# B12356-04b.net
KiCad netlist of a schematic drawn in EAGLE
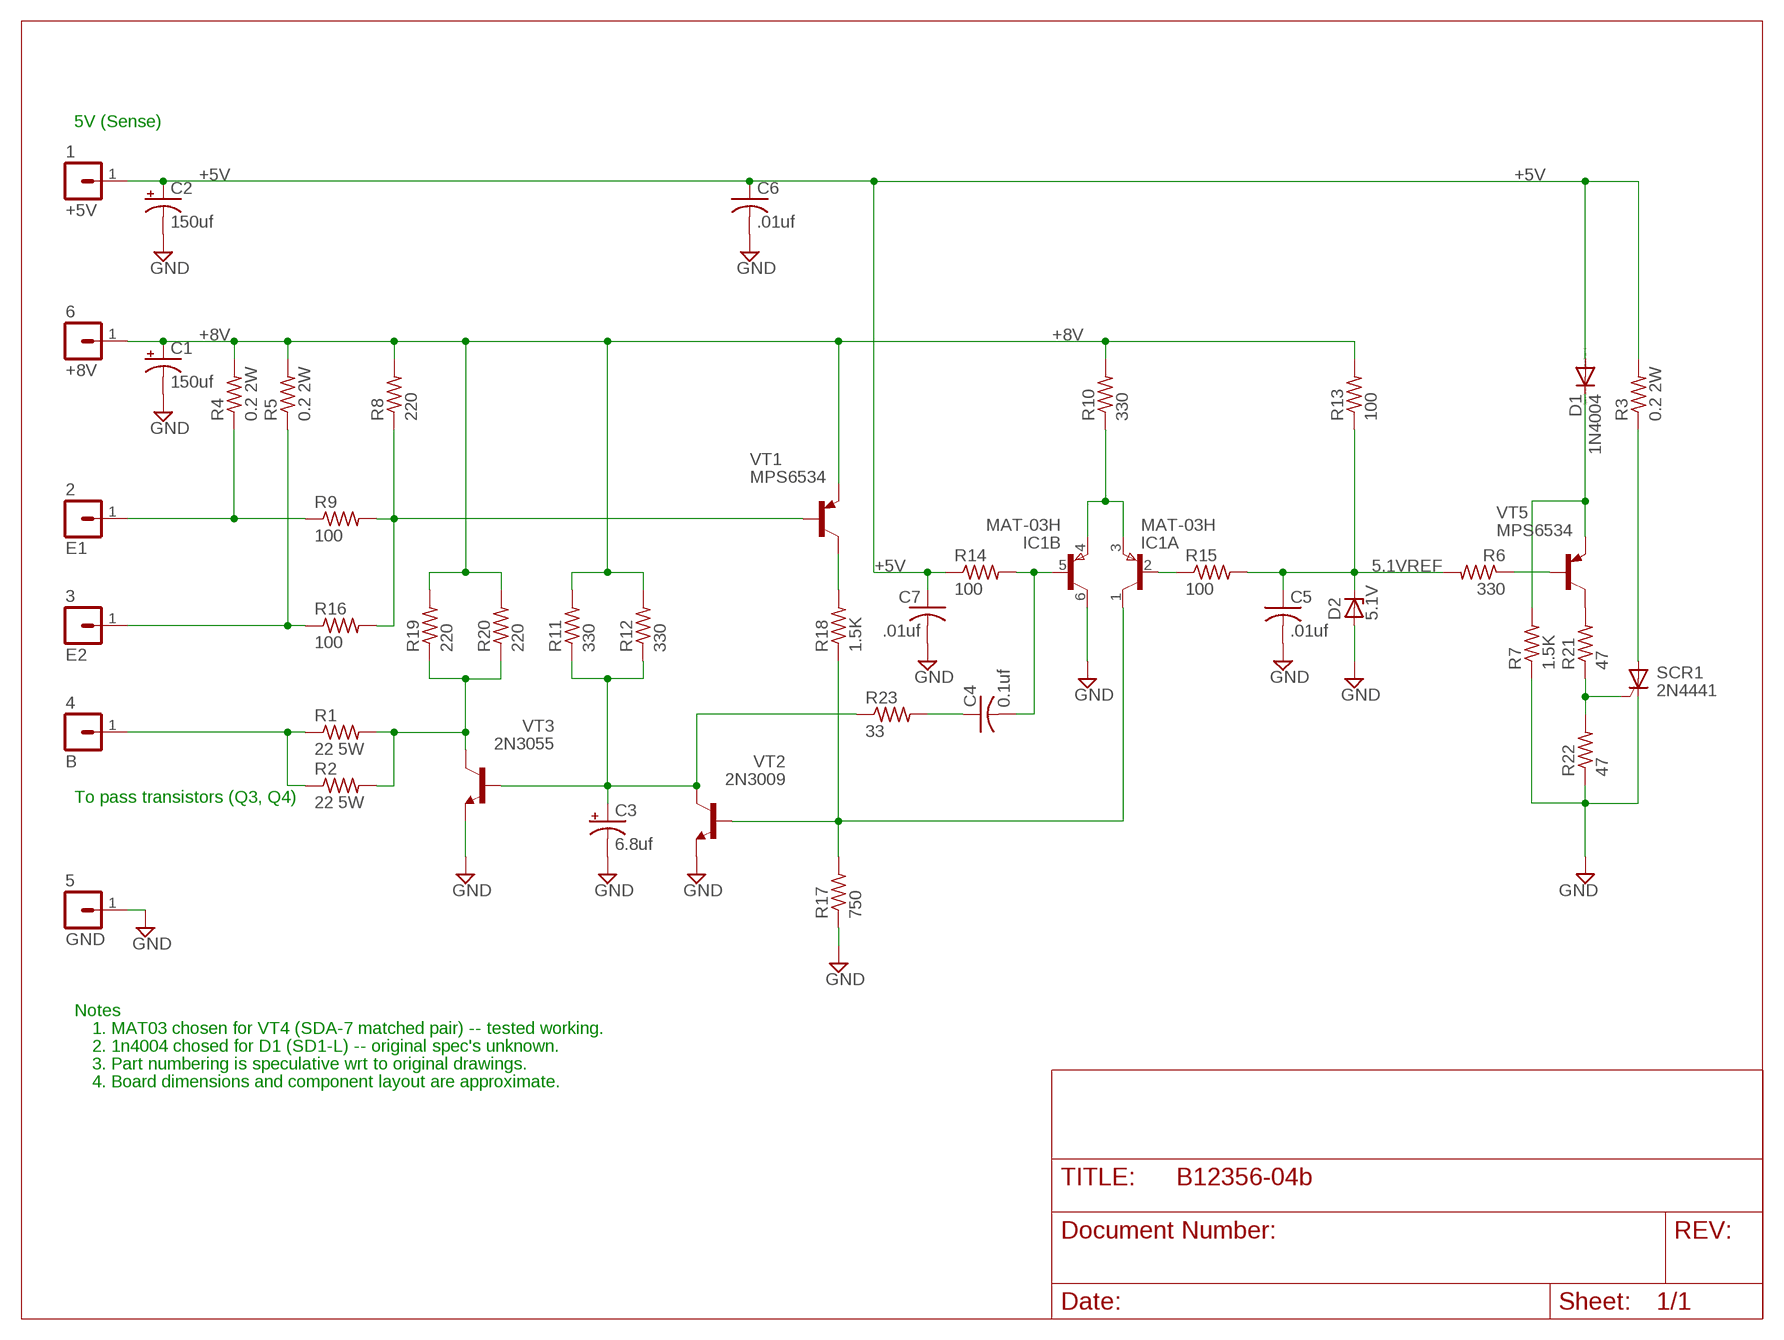
[diagram p0: schematic, sheet 1]

(export (version "E")
  (design (tool "Eeschema 10.0.6"))
  (components
    (comp (ref "+5V")
      (value "1")
      (footprint "eagle-import:SPADELUG")
      (libsource (lib "eagle-import") (part "LUG"))
    )
    (comp (ref "+8V")
      (value "6")
      (footprint "eagle-import:SPADELUG")
      (libsource (lib "eagle-import") (part "LUG"))
    )
    (comp (ref "B")
      (value "4")
      (footprint "eagle-import:SPADELUG")
      (libsource (lib "eagle-import") (part "LUG"))
    )
    (comp (ref "C1")
      (value "150uf")
      (footprint "eagle-import:E30-10")
      (libsource (lib "eagle-import") (part "CPOL-USE30-10AXIAL"))
    )
    (comp (ref "C2")
      (value "150uf")
      (footprint "eagle-import:E25-9")
      (libsource (lib "eagle-import") (part "CPOL-USE25-9AXIAL"))
    )
    (comp (ref "C3")
      (value "6.8uf")
      (footprint "eagle-import:E22-6")
      (libsource (lib "eagle-import") (part "CPOL-USE22-6AXIAL"))
    )
    (comp (ref "C4")
      (value "0.1uf")
      (footprint "eagle-import:C150-054X183")
      (libsource (lib "eagle-import") (part "C-US150-054X183"))
    )
    (comp (ref "C5")
      (value ".01uf")
      (footprint "eagle-import:C050-025X075")
      (libsource (lib "eagle-import") (part "C-US050-025X075"))
    )
    (comp (ref "C6")
      (value ".01uf")
      (footprint "eagle-import:C050-025X075")
      (libsource (lib "eagle-import") (part "C-US050-025X075"))
    )
    (comp (ref "C7")
      (value ".01uf")
      (footprint "eagle-import:C050-025X075")
      (libsource (lib "eagle-import") (part "C-US050-025X075"))
    )
    (comp (ref "D1")
      (value "1N4004")
      (footprint "eagle-import:DO41-10")
      (libsource (lib "eagle-import") (part "1N4004"))
    )
    (comp (ref "D2")
      (value "5.1V")
      (footprint "eagle-import:F126Z12")
      (libsource (lib "eagle-import") (part "ZENER-DIODEF126-12"))
    )
    (comp (ref "E1")
      (value "2")
      (footprint "eagle-import:SPADELUG")
      (libsource (lib "eagle-import") (part "LUG"))
    )
    (comp (ref "E2")
      (value "3")
      (footprint "eagle-import:SPADELUG")
      (libsource (lib "eagle-import") (part "LUG"))
    )
    (comp (ref "GND")
      (value "5")
      (footprint "eagle-import:SPADELUG")
      (libsource (lib "eagle-import") (part "LUG"))
    )
    (comp (ref "IC1")
      (value "MAT-03H")
      (footprint "eagle-import:TO78")
      (libsource (lib "eagle-import") (part "MAT-03H"))
    )
    (comp (ref "R1")
      (value "22 5W")
      (footprint "eagle-import:P0817_22")
      (libsource (lib "eagle-import") (part "R-US_0817/22"))
    )
    (comp (ref "R2")
      (value "22 5W")
      (footprint "eagle-import:P0817_22")
      (libsource (lib "eagle-import") (part "R-US_0817/22"))
    )
    (comp (ref "R3")
      (value "0.2 2W")
      (footprint "eagle-import:0617_22")
      (libsource (lib "eagle-import") (part "R-US_0617/22"))
    )
    (comp (ref "R4")
      (value "0.2 2W")
      (footprint "eagle-import:0617_22")
      (libsource (lib "eagle-import") (part "R-US_0617/22"))
    )
    (comp (ref "R5")
      (value "0.2 2W")
      (footprint "eagle-import:0617_22")
      (libsource (lib "eagle-import") (part "R-US_0617/22"))
    )
    (comp (ref "R6")
      (value "330")
      (footprint "eagle-import:0207_12")
      (libsource (lib "eagle-import") (part "R-US_0207/12"))
    )
    (comp (ref "R7")
      (value "1.5K")
      (footprint "eagle-import:0207_12")
      (libsource (lib "eagle-import") (part "R-US_0207/12"))
    )
    (comp (ref "R8")
      (value "220")
      (footprint "eagle-import:0207_12")
      (libsource (lib "eagle-import") (part "R-US_0207/12"))
    )
    (comp (ref "R9")
      (value "100")
      (footprint "eagle-import:0207_12")
      (libsource (lib "eagle-import") (part "R-US_0207/12"))
    )
    (comp (ref "R10")
      (value "330")
      (footprint "eagle-import:0207_12")
      (libsource (lib "eagle-import") (part "R-US_0207/12"))
    )
    (comp (ref "R11")
      (value "330")
      (footprint "eagle-import:0207_12")
      (libsource (lib "eagle-import") (part "R-US_0207/12"))
    )
    (comp (ref "R12")
      (value "330")
      (footprint "eagle-import:0207_12")
      (libsource (lib "eagle-import") (part "R-US_0207/12"))
    )
    (comp (ref "R13")
      (value "100")
      (footprint "eagle-import:0207_12")
      (libsource (lib "eagle-import") (part "R-US_0207/12"))
    )
    (comp (ref "R14")
      (value "100")
      (footprint "eagle-import:0207_12")
      (libsource (lib "eagle-import") (part "R-US_0207/12"))
    )
    (comp (ref "R15")
      (value "100")
      (footprint "eagle-import:0207_12")
      (libsource (lib "eagle-import") (part "R-US_0207/12"))
    )
    (comp (ref "R16")
      (value "100")
      (footprint "eagle-import:0207_12")
      (libsource (lib "eagle-import") (part "R-US_0207/12"))
    )
    (comp (ref "R17")
      (value "750")
      (footprint "eagle-import:0207_10")
      (libsource (lib "eagle-import") (part "R-US_0207/10"))
    )
    (comp (ref "R18")
      (value "1.5K")
      (footprint "eagle-import:0207_10")
      (libsource (lib "eagle-import") (part "R-US_0207/10"))
    )
    (comp (ref "R19")
      (value "220")
      (footprint "eagle-import:0207_12")
      (libsource (lib "eagle-import") (part "R-US_0207/12"))
    )
    (comp (ref "R20")
      (value "220")
      (footprint "eagle-import:0207_12")
      (libsource (lib "eagle-import") (part "R-US_0207/12"))
    )
    (comp (ref "R21")
      (value "47")
      (footprint "eagle-import:0207_12")
      (libsource (lib "eagle-import") (part "R-US_0207/12"))
    )
    (comp (ref "R22")
      (value "47")
      (footprint "eagle-import:0207_12")
      (libsource (lib "eagle-import") (part "R-US_0207/12"))
    )
    (comp (ref "R23")
      (value "33")
      (footprint "eagle-import:0207_12")
      (libsource (lib "eagle-import") (part "R-US_0207/12"))
    )
    (comp (ref "SCR1")
      (value "2N4441")
      (footprint "eagle-import:TO220CL")
      (libsource (lib "eagle-import") (part "BT151"))
    )
    (comp (ref "VT1")
      (value "MPS6534")
      (footprint "eagle-import:TO92-BCE")
      (libsource (lib "eagle-import") (part "-PNP-TO92-BCEMPSA56"))
    )
    (comp (ref "VT2")
      (value "2N3009")
      (footprint "eagle-import:TO18")
      (libsource (lib "eagle-import") (part "2N2222"))
    )
    (comp (ref "VT3")
      (value "2N3055")
      (footprint "eagle-import:TO3")
      (libsource (lib "eagle-import") (part "2N3055"))
    )
    (comp (ref "VT5")
      (value "MPS6534")
      (footprint "eagle-import:TO92-BCE")
      (libsource (lib "eagle-import") (part "-PNP-TO92-BCEMPSA56"))
    )
  )
  (nets
    (net (code "1") (name "/+5V") (class "Default")
      (node (ref "+5V") (pin "1") (pinfunction "1_1") (pintype "passive"))
      (node (ref "C2") (pin "+") (pinfunction "+_+") (pintype "passive"))
      (node (ref "C6") (pin "1") (pinfunction "1_1") (pintype "passive"))
      (node (ref "C7") (pin "1") (pinfunction "1_1") (pintype "passive"))
      (node (ref "D1") (pin "A") (pinfunction "A_A") (pintype "passive"))
      (node (ref "R14") (pin "1") (pinfunction "1_1") (pintype "passive"))
      (node (ref "R3") (pin "2") (pinfunction "2_2") (pintype "passive"))
    )
    (net (code "2") (name "/+8V") (class "Default")
      (node (ref "+8V") (pin "1") (pinfunction "1_1") (pintype "passive"))
      (node (ref "C1") (pin "+") (pinfunction "+_+") (pintype "passive"))
      (node (ref "R10") (pin "2") (pinfunction "2_2") (pintype "passive"))
      (node (ref "R11") (pin "2") (pinfunction "2_2") (pintype "passive"))
      (node (ref "R12") (pin "2") (pinfunction "2_2") (pintype "passive"))
      (node (ref "R13") (pin "2") (pinfunction "2_2") (pintype "passive"))
      (node (ref "R19") (pin "2") (pinfunction "2_2") (pintype "passive"))
      (node (ref "R20") (pin "2") (pinfunction "2_2") (pintype "passive"))
      (node (ref "R4") (pin "2") (pinfunction "2_2") (pintype "passive"))
      (node (ref "R5") (pin "2") (pinfunction "2_2") (pintype "passive"))
      (node (ref "R8") (pin "2") (pinfunction "2_2") (pintype "passive"))
      (node (ref "VT1") (pin "E") (pinfunction "E_E") (pintype "passive"))
    )
    (net (code "3") (name "/5.1VREF") (class "Default")
      (node (ref "C5") (pin "1") (pinfunction "1_1") (pintype "passive"))
      (node (ref "D2") (pin "C") (pinfunction "C_C") (pintype "passive"))
      (node (ref "R13") (pin "1") (pinfunction "1_1") (pintype "passive"))
      (node (ref "R15") (pin "2") (pinfunction "2_2") (pintype "passive"))
      (node (ref "R6") (pin "2") (pinfunction "2_2") (pintype "passive"))
    )
    (net (code "4") (name "GND") (class "Default")
      (node (ref "C1") (pin "-") (pinfunction "-_-") (pintype "passive"))
      (node (ref "C2") (pin "-") (pinfunction "-_-") (pintype "passive"))
      (node (ref "C3") (pin "-") (pinfunction "-_-") (pintype "passive"))
      (node (ref "C5") (pin "2") (pinfunction "2_2") (pintype "passive"))
      (node (ref "C6") (pin "2") (pinfunction "2_2") (pintype "passive"))
      (node (ref "C7") (pin "2") (pinfunction "2_2") (pintype "passive"))
      (node (ref "D2") (pin "A") (pinfunction "A_A") (pintype "passive"))
      (node (ref "GND") (pin "1") (pinfunction "1_1") (pintype "passive"))
      (node (ref "IC1") (pin "6") (pinfunction "C_6") (pintype "passive"))
      (node (ref "R17") (pin "1") (pinfunction "1_1") (pintype "passive"))
      (node (ref "R22") (pin "1") (pinfunction "1_1") (pintype "passive"))
      (node (ref "R7") (pin "1") (pinfunction "1_1") (pintype "passive"))
      (node (ref "SCR1") (pin "C") (pinfunction "C_C") (pintype "passive"))
      (node (ref "VT2") (pin "1") (pinfunction "E_1") (pintype "passive"))
      (node (ref "VT3") (pin "E") (pinfunction "E_E") (pintype "passive"))
    )
    (net (code "5") (name "Net-(B-Pad1)") (class "Default")
      (node (ref "B") (pin "1") (pinfunction "1_1") (pintype "passive"))
      (node (ref "R1") (pin "1") (pinfunction "1_1") (pintype "passive"))
      (node (ref "R2") (pin "1") (pinfunction "1_1") (pintype "passive"))
    )
    (net (code "6") (name "Net-(C4-Pad1)") (class "Default")
      (node (ref "C4") (pin "1") (pinfunction "1_1") (pintype "passive"))
      (node (ref "R23") (pin "2") (pinfunction "2_2") (pintype "passive"))
    )
    (net (code "7") (name "Net-(D1-PadC)") (class "Default")
      (node (ref "D1") (pin "C") (pinfunction "C_C") (pintype "passive"))
      (node (ref "R7") (pin "2") (pinfunction "2_2") (pintype "passive"))
      (node (ref "VT5") (pin "E") (pinfunction "E_E") (pintype "passive"))
    )
    (net (code "8") (name "Net-(E1-Pad1)") (class "Default")
      (node (ref "E1") (pin "1") (pinfunction "1_1") (pintype "passive"))
      (node (ref "R4") (pin "1") (pinfunction "1_1") (pintype "passive"))
      (node (ref "R9") (pin "1") (pinfunction "1_1") (pintype "passive"))
    )
    (net (code "9") (name "Net-(E2-Pad1)") (class "Default")
      (node (ref "E2") (pin "1") (pinfunction "1_1") (pintype "passive"))
      (node (ref "R16") (pin "1") (pinfunction "1_1") (pintype "passive"))
      (node (ref "R5") (pin "1") (pinfunction "1_1") (pintype "passive"))
    )
    (net (code "10") (name "Net-(IC1A-B)") (class "Default")
      (node (ref "IC1") (pin "2") (pinfunction "B_2") (pintype "passive"))
      (node (ref "R15") (pin "1") (pinfunction "1_1") (pintype "passive"))
    )
    (net (code "11") (name "Net-(IC1A-C)") (class "Default")
      (node (ref "IC1") (pin "1") (pinfunction "C_1") (pintype "passive"))
      (node (ref "R17") (pin "2") (pinfunction "2_2") (pintype "passive"))
      (node (ref "R18") (pin "1") (pinfunction "1_1") (pintype "passive"))
      (node (ref "VT2") (pin "2") (pinfunction "B_2") (pintype "passive"))
    )
    (net (code "12") (name "Net-(IC1A-E)") (class "Default")
      (node (ref "IC1") (pin "3") (pinfunction "E_3") (pintype "passive"))
      (node (ref "IC1") (pin "4") (pinfunction "E_4") (pintype "passive"))
      (node (ref "R10") (pin "1") (pinfunction "1_1") (pintype "passive"))
    )
    (net (code "13") (name "Net-(IC1B-B)") (class "Default")
      (node (ref "C4") (pin "2") (pinfunction "2_2") (pintype "passive"))
      (node (ref "IC1") (pin "5") (pinfunction "B_5") (pintype "passive"))
      (node (ref "R14") (pin "2") (pinfunction "2_2") (pintype "passive"))
    )
    (net (code "14") (name "Net-(R1-Pad2)") (class "Default")
      (node (ref "R1") (pin "2") (pinfunction "2_2") (pintype "passive"))
      (node (ref "R19") (pin "1") (pinfunction "1_1") (pintype "passive"))
      (node (ref "R2") (pin "2") (pinfunction "2_2") (pintype "passive"))
      (node (ref "R20") (pin "1") (pinfunction "1_1") (pintype "passive"))
      (node (ref "VT3") (pin "C") (pinfunction "C_C") (pintype "passive"))
      (node (ref "VT3") (pin "C/") (pinfunction "C_C/") (pintype "passive"))
    )
    (net (code "15") (name "Net-(R3-Pad1)") (class "Default")
      (node (ref "R3") (pin "1") (pinfunction "1_1") (pintype "passive"))
      (node (ref "SCR1") (pin "A") (pinfunction "A_A") (pintype "passive"))
    )
    (net (code "16") (name "Net-(R6-Pad1)") (class "Default")
      (node (ref "R6") (pin "1") (pinfunction "1_1") (pintype "passive"))
      (node (ref "VT5") (pin "B") (pinfunction "B_B") (pintype "passive"))
    )
    (net (code "17") (name "Net-(R16-Pad2)") (class "Default")
      (node (ref "R16") (pin "2") (pinfunction "2_2") (pintype "passive"))
      (node (ref "R8") (pin "1") (pinfunction "1_1") (pintype "passive"))
      (node (ref "R9") (pin "2") (pinfunction "2_2") (pintype "passive"))
      (node (ref "VT1") (pin "B") (pinfunction "B_B") (pintype "passive"))
    )
    (net (code "18") (name "Net-(R18-Pad2)") (class "Default")
      (node (ref "R18") (pin "2") (pinfunction "2_2") (pintype "passive"))
      (node (ref "VT1") (pin "C") (pinfunction "C_C") (pintype "passive"))
    )
    (net (code "19") (name "Net-(R21-Pad1)") (class "Default")
      (node (ref "R21") (pin "1") (pinfunction "1_1") (pintype "passive"))
      (node (ref "R22") (pin "2") (pinfunction "2_2") (pintype "passive"))
      (node (ref "SCR1") (pin "G") (pinfunction "G_G") (pintype "passive"))
    )
    (net (code "20") (name "Net-(R21-Pad2)") (class "Default")
      (node (ref "R21") (pin "2") (pinfunction "2_2") (pintype "passive"))
      (node (ref "VT5") (pin "C") (pinfunction "C_C") (pintype "passive"))
    )
    (net (code "21") (name "Net-(VT2-C)") (class "Default")
      (node (ref "C3") (pin "+") (pinfunction "+_+") (pintype "passive"))
      (node (ref "R11") (pin "1") (pinfunction "1_1") (pintype "passive"))
      (node (ref "R12") (pin "1") (pinfunction "1_1") (pintype "passive"))
      (node (ref "R23") (pin "1") (pinfunction "1_1") (pintype "passive"))
      (node (ref "VT2") (pin "3") (pinfunction "C_3") (pintype "passive"))
      (node (ref "VT3") (pin "B") (pinfunction "B_B") (pintype "passive"))
    )
  )
)
